# UPCNSL_ABS_RF_POL.net
KiCad netlist of a schematic drawn in Altium Designer
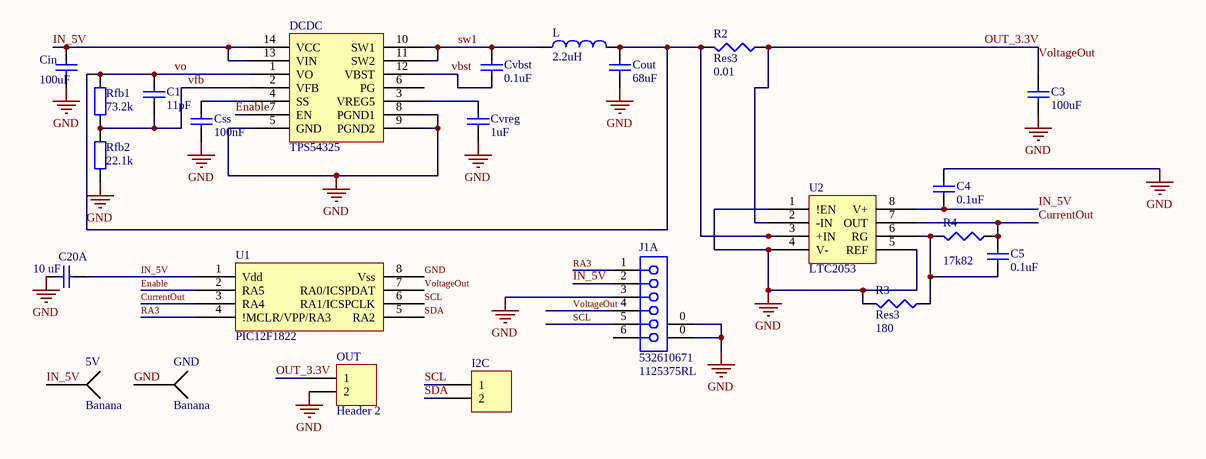
[diagram p0: UPCNSL_ABS_RF_POL.SchDoc]

(export (version "E")
  (design (tool "Eeschema 10.0.6"))
  (components
    (comp (ref "5V")
      (value "Banana")
      (footprint "Banana")
      (libsource (lib "UPCNSL_ABS_EPS_POL") (part "Banana"))
    )
    (comp (ref "C1")
      (value "11pF")
      (footprint "CAP0603")
      (description "Capacitor")
      (fields (field (name "Comment") "CAP0603"))
      (libsource (lib "UPCNSL-ABS-FLS-ARD_v1.2") (part "CAP0603"))
    )
    (comp (ref "C3")
      (value "100uF")
      (footprint "CAP0603")
      (description "Capacitor")
      (fields (field (name "Comment") "CAP0603"))
      (libsource (lib "EPS") (part "CAP0603"))
    )
    (comp (ref "C4")
      (value "0.1uF")
      (footprint "CAP0603")
      (description "Capacitor")
      (fields (field (name "Comment") "CAP0603"))
      (libsource (lib "EPS") (part "CAP0603"))
    )
    (comp (ref "C5")
      (value "0.1uF")
      (footprint "CAP0603")
      (description "Capacitor")
      (fields (field (name "Comment") "CAP0603"))
      (libsource (lib "EPS") (part "CAP0603"))
    )
    (comp (ref "C20A")
      (value "10 uF")
      (footprint "CAP0603")
      (description "Capacitor (Semiconductor SIM Model)")
      (fields (field (name "Comment") "Cap Semi") (field (name "PUBLISHER") "Altium Limited"))
      (libsource (lib "Miscellaneous Devices") (part "Cap Semi"))
    )
    (comp (ref "Cin")
      (value "100uF")
      (footprint "CAP0603")
      (description "Capacitor")
      (fields (field (name "Comment") "CAP0603"))
      (libsource (lib "UPCNSL-ABS-FLS-ARD_v1.2") (part "CAP0603"))
    )
    (comp (ref "Cout")
      (value "68uF")
      (footprint "CAP0603")
      (description "Capacitor")
      (fields (field (name "Comment") "CAP0603"))
      (libsource (lib "UPCNSL-ABS-FLS-ARD_v1.2") (part "CAP0603"))
    )
    (comp (ref "Css")
      (value "100nF")
      (footprint "CAP0603")
      (description "Capacitor")
      (fields (field (name "Comment") "CAP0603"))
      (libsource (lib "UPCNSL-ABS-FLS-ARD_v1.2") (part "CAP0603"))
    )
    (comp (ref "Cvbst")
      (value "0.1uF")
      (footprint "CAP0603")
      (description "Capacitor")
      (fields (field (name "Comment") "CAP0603"))
      (libsource (lib "UPCNSL-ABS-FLS-ARD_v1.2") (part "CAP0603"))
    )
    (comp (ref "Cvreg")
      (value "1uF")
      (footprint "CAP0603")
      (description "Capacitor")
      (fields (field (name "Comment") "CAP0603"))
      (libsource (lib "UPCNSL-ABS-FLS-ARD_v1.2") (part "CAP0603"))
    )
    (comp (ref "DCDC")
      (value "TPS54325")
      (footprint "TPS54325")
      (libsource (lib "UPCNSL_ABS_EPS_POL") (part "TPS54325"))
    )
    (comp (ref "GND")
      (value "Banana")
      (footprint "Banana")
      (libsource (lib "UPCNSL_ABS_EPS_POL") (part "Banana"))
    )
    (comp (ref "I2C")
      (value "Header 2")
      (footprint "HDR1X2")
      (description "Header, 2-Pin")
      (fields (field (name "PUBLISHER") "Altium Limited"))
      (libsource (lib "Miscellaneous Connectors") (part "Header 2"))
    )
    (comp (ref "J1A")
      (value "532610671")
      (footprint "532610671")
      (description "1.25mm Pitch PicoBlade™ Header, Surface Mount, Right Angle, Lead-Free, 6 Circuits")
      (fields (field (name "SUPPLIER PART NUMBER 1") "1125375RL"))
      (libsource (lib "3CAT_Connectors") (part "MOLEX_532610671"))
    )
    (comp (ref "L")
      (value "2.2uH")
      (footprint "L_DCDC_TPS54325_v2")
      (libsource (lib "UPCNSL_ABS_EPS_POL") (part "L_DCDC_TPS54325"))
    )
    (comp (ref "OUT")
      (value "Header 2")
      (footprint "HDR1X2")
      (description "Header, 2-Pin")
      (fields (field (name "PUBLISHER") "Altium Limited"))
      (libsource (lib "Miscellaneous Connectors") (part "Header 2"))
    )
    (comp (ref "R2")
      (value "Res3")
      (footprint "J1-0603")
      (description "Resistor")
      (fields (field (name "ALTIUM_VALUE") "0.01") (field (name "PUBLISHER") "Altium Limited"))
      (libsource (lib "Miscellaneous Devices") (part "Res3"))
    )
    (comp (ref "R3")
      (value "Res3")
      (footprint "J1-0603")
      (description "Resistor")
      (fields (field (name "ALTIUM_VALUE") "180") (field (name "PUBLISHER") "Altium Limited"))
      (libsource (lib "Miscellaneous Devices") (part "Res3"))
    )
    (comp (ref "R4")
      (value "17k82")
      (footprint "J1-0603")
      (description "Resistor")
      (fields (field (name "Comment") "Res3") (field (name "PUBLISHER") "Altium Limited"))
      (libsource (lib "Miscellaneous Devices") (part "Res3"))
    )
    (comp (ref "Rfb1")
      (value "73.2k")
      (footprint "RES0603")
      (description "Resistor")
      (fields (field (name "Comment") "RES0603"))
      (libsource (lib "EPS") (part "RES0603"))
    )
    (comp (ref "Rfb2")
      (value "22.1k")
      (footprint "RES0603")
      (description "Resistor")
      (fields (field (name "Comment") "RES0603"))
      (libsource (lib "EPS") (part "RES0603"))
    )
    (comp (ref "U1")
      (value "PIC12F1822")
      (footprint "PIC12F1822")
      (libsource (lib "UPCNSL_ABS_EPS_POL") (part "PIC12F1822"))
    )
    (comp (ref "U2")
      (value "LTC2053")
      (footprint "LTC2053 IPC")
      (libsource (lib "UPCNSL_ABS_EPS_POL") (part "LTC2053"))
    )
  )
  (nets
    (net (code "1") (name "/CurrentOut") (class "Default")
      (node (ref "C5") (pin "1") (pinfunction "1_1") (pintype "passive"))
      (node (ref "R4") (pin "1") (pinfunction "1_1") (pintype "passive"))
      (node (ref "U1") (pin "3") (pinfunction "RA4_3") (pintype "passive"))
      (node (ref "U2") (pin "7") (pinfunction "OUT_7") (pintype "passive"))
    )
    (net (code "2") (name "/Enable") (class "Default")
      (node (ref "DCDC") (pin "7") (pinfunction "EN_7") (pintype "passive"))
      (node (ref "U1") (pin "2") (pinfunction "RA5_2") (pintype "passive"))
    )
    (net (code "3") (name "/IN_5V") (class "Default")
      (node (ref "5V") (pin "1") (pinfunction "1_1") (pintype "passive"))
      (node (ref "C20A") (pin "1") (pinfunction "1_1") (pintype "passive"))
      (node (ref "C4") (pin "2") (pinfunction "2_2") (pintype "passive"))
      (node (ref "Cin") (pin "2") (pinfunction "2_2") (pintype "passive"))
      (node (ref "DCDC") (pin "13") (pinfunction "VIN_13") (pintype "passive"))
      (node (ref "DCDC") (pin "14") (pinfunction "VCC_14") (pintype "passive"))
      (node (ref "J1A") (pin "2") (pinfunction "2_2") (pintype "passive"))
      (node (ref "U1") (pin "1") (pinfunction "Vdd_1") (pintype "power_in"))
      (node (ref "U2") (pin "8") (pinfunction "V+_8") (pintype "power_in"))
    )
    (net (code "4") (name "/OUT_3.3V") (class "Default")
      (node (ref "C3") (pin "1") (pinfunction "1_1") (pintype "passive"))
      (node (ref "J1A") (pin "4") (pinfunction "4_4") (pintype "passive"))
      (node (ref "OUT") (pin "1") (pinfunction "1_1") (pintype "passive"))
      (node (ref "R2") (pin "1") (pinfunction "1_1") (pintype "passive"))
      (node (ref "U1") (pin "7") (pinfunction "RA0/ICSPDAT_7") (pintype "passive"))
      (node (ref "U2") (pin "2") (pinfunction "-IN_2") (pintype "passive"))
    )
    (net (code "5") (name "/RA3") (class "Default")
      (node (ref "J1A") (pin "1") (pinfunction "1_1") (pintype "passive"))
      (node (ref "U1") (pin "4") (pinfunction "!MCLR/VPP/RA3_4") (pintype "passive"))
    )
    (net (code "6") (name "/SCL") (class "Default")
      (node (ref "I2C") (pin "1") (pinfunction "1_1") (pintype "passive"))
      (node (ref "J1A") (pin "5") (pinfunction "5_5") (pintype "passive"))
      (node (ref "U1") (pin "6") (pinfunction "RA1/ICSPCLK_6") (pintype "passive"))
    )
    (net (code "7") (name "/SDA") (class "Default")
      (node (ref "I2C") (pin "2") (pinfunction "2_2") (pintype "passive"))
      (node (ref "U1") (pin "5") (pinfunction "RA2_5") (pintype "passive"))
    )
    (net (code "8") (name "/sw1") (class "Default")
      (node (ref "Cvbst") (pin "2") (pinfunction "2_2") (pintype "passive"))
      (node (ref "DCDC") (pin "10") (pinfunction "SW1_10") (pintype "passive"))
      (node (ref "DCDC") (pin "11") (pinfunction "SW2_11") (pintype "passive"))
      (node (ref "L") (pin "1") (pinfunction "1_1") (pintype "passive"))
    )
    (net (code "9") (name "/vbst") (class "Default")
      (node (ref "Cvbst") (pin "1") (pinfunction "1_1") (pintype "passive"))
      (node (ref "DCDC") (pin "12") (pinfunction "VBST_12") (pintype "passive"))
    )
    (net (code "10") (name "/vfb") (class "Default")
      (node (ref "C1") (pin "1") (pinfunction "1_1") (pintype "passive"))
      (node (ref "DCDC") (pin "2") (pinfunction "VFB_2") (pintype "passive"))
      (node (ref "Rfb1") (pin "1") (pinfunction "1_1") (pintype "passive"))
      (node (ref "Rfb2") (pin "2") (pinfunction "2_2") (pintype "passive"))
    )
    (net (code "11") (name "/vo") (class "Default")
      (node (ref "C1") (pin "2") (pinfunction "2_2") (pintype "passive"))
      (node (ref "Cout") (pin "2") (pinfunction "2_2") (pintype "passive"))
      (node (ref "DCDC") (pin "1") (pinfunction "VO_1") (pintype "passive"))
      (node (ref "L") (pin "2") (pinfunction "2_2") (pintype "passive"))
      (node (ref "R2") (pin "2") (pinfunction "2_2") (pintype "passive"))
      (node (ref "Rfb1") (pin "2") (pinfunction "2_2") (pintype "passive"))
      (node (ref "U2") (pin "3") (pinfunction "+IN_3") (pintype "passive"))
    )
    (net (code "12") (name "GND") (class "Default")
      (node (ref "C20A") (pin "2") (pinfunction "2_2") (pintype "passive"))
      (node (ref "C3") (pin "2") (pinfunction "2_2") (pintype "passive"))
      (node (ref "C4") (pin "1") (pinfunction "1_1") (pintype "passive"))
      (node (ref "Cin") (pin "1") (pinfunction "1_1") (pintype "passive"))
      (node (ref "Cout") (pin "1") (pinfunction "1_1") (pintype "passive"))
      (node (ref "Css") (pin "1") (pinfunction "1_1") (pintype "passive"))
      (node (ref "Cvreg") (pin "1") (pinfunction "1_1") (pintype "passive"))
      (node (ref "DCDC") (pin "5") (pinfunction "GND_5") (pintype "passive"))
      (node (ref "DCDC") (pin "8") (pinfunction "PGND1_8") (pintype "passive"))
      (node (ref "DCDC") (pin "9") (pinfunction "PGND2_9") (pintype "passive"))
      (node (ref "GND") (pin "1") (pinfunction "1_1") (pintype "passive"))
      (node (ref "J1A") (pin "0") (pinfunction "MH1_0") (pintype "passive"))
      (node (ref "J1A") (pin "3") (pinfunction "3_3") (pintype "passive"))
      (node (ref "OUT") (pin "2") (pinfunction "2_2") (pintype "passive"))
      (node (ref "R3") (pin "2") (pinfunction "2_2") (pintype "passive"))
      (node (ref "Rfb2") (pin "1") (pinfunction "1_1") (pintype "passive"))
      (node (ref "U1") (pin "8") (pinfunction "Vss_8") (pintype "power_in"))
      (node (ref "U2") (pin "1") (pinfunction "!EN_1") (pintype "passive"))
      (node (ref "U2") (pin "4") (pinfunction "V-_4") (pintype "power_in"))
      (node (ref "U2") (pin "5") (pinfunction "REF_5") (pintype "passive"))
    )
    (net (code "13") (name "Net-(DCDC-SS)") (class "Default")
      (node (ref "Css") (pin "2") (pinfunction "2_2") (pintype "passive"))
      (node (ref "DCDC") (pin "4") (pinfunction "SS_4") (pintype "passive"))
    )
    (net (code "14") (name "Net-(DCDC-VREG5)") (class "Default")
      (node (ref "Cvreg") (pin "2") (pinfunction "2_2") (pintype "passive"))
      (node (ref "DCDC") (pin "3") (pinfunction "VREG5_3") (pintype "passive"))
    )
    (net (code "15") (name "Net-(U2-RG)") (class "Default")
      (node (ref "C5") (pin "2") (pinfunction "2_2") (pintype "passive"))
      (node (ref "R3") (pin "1") (pinfunction "1_1") (pintype "passive"))
      (node (ref "R4") (pin "2") (pinfunction "2_2") (pintype "passive"))
      (node (ref "U2") (pin "6") (pinfunction "RG_6") (pintype "passive"))
    )
    (net (code "16") (name "unconnected-(DCDC-PG-Pad6)") (class "Default")
      (node (ref "DCDC") (pin "6") (pinfunction "PG_6") (pintype "passive"))
    )
    (net (code "17") (name "unconnected-(J1A-Pad6)") (class "Default")
      (node (ref "J1A") (pin "6") (pinfunction "6_6") (pintype "passive"))
    )
  )
)
